# NODE_DW1000_B_V2.net
KiCad netlist of a schematic drawn in Altium Designer
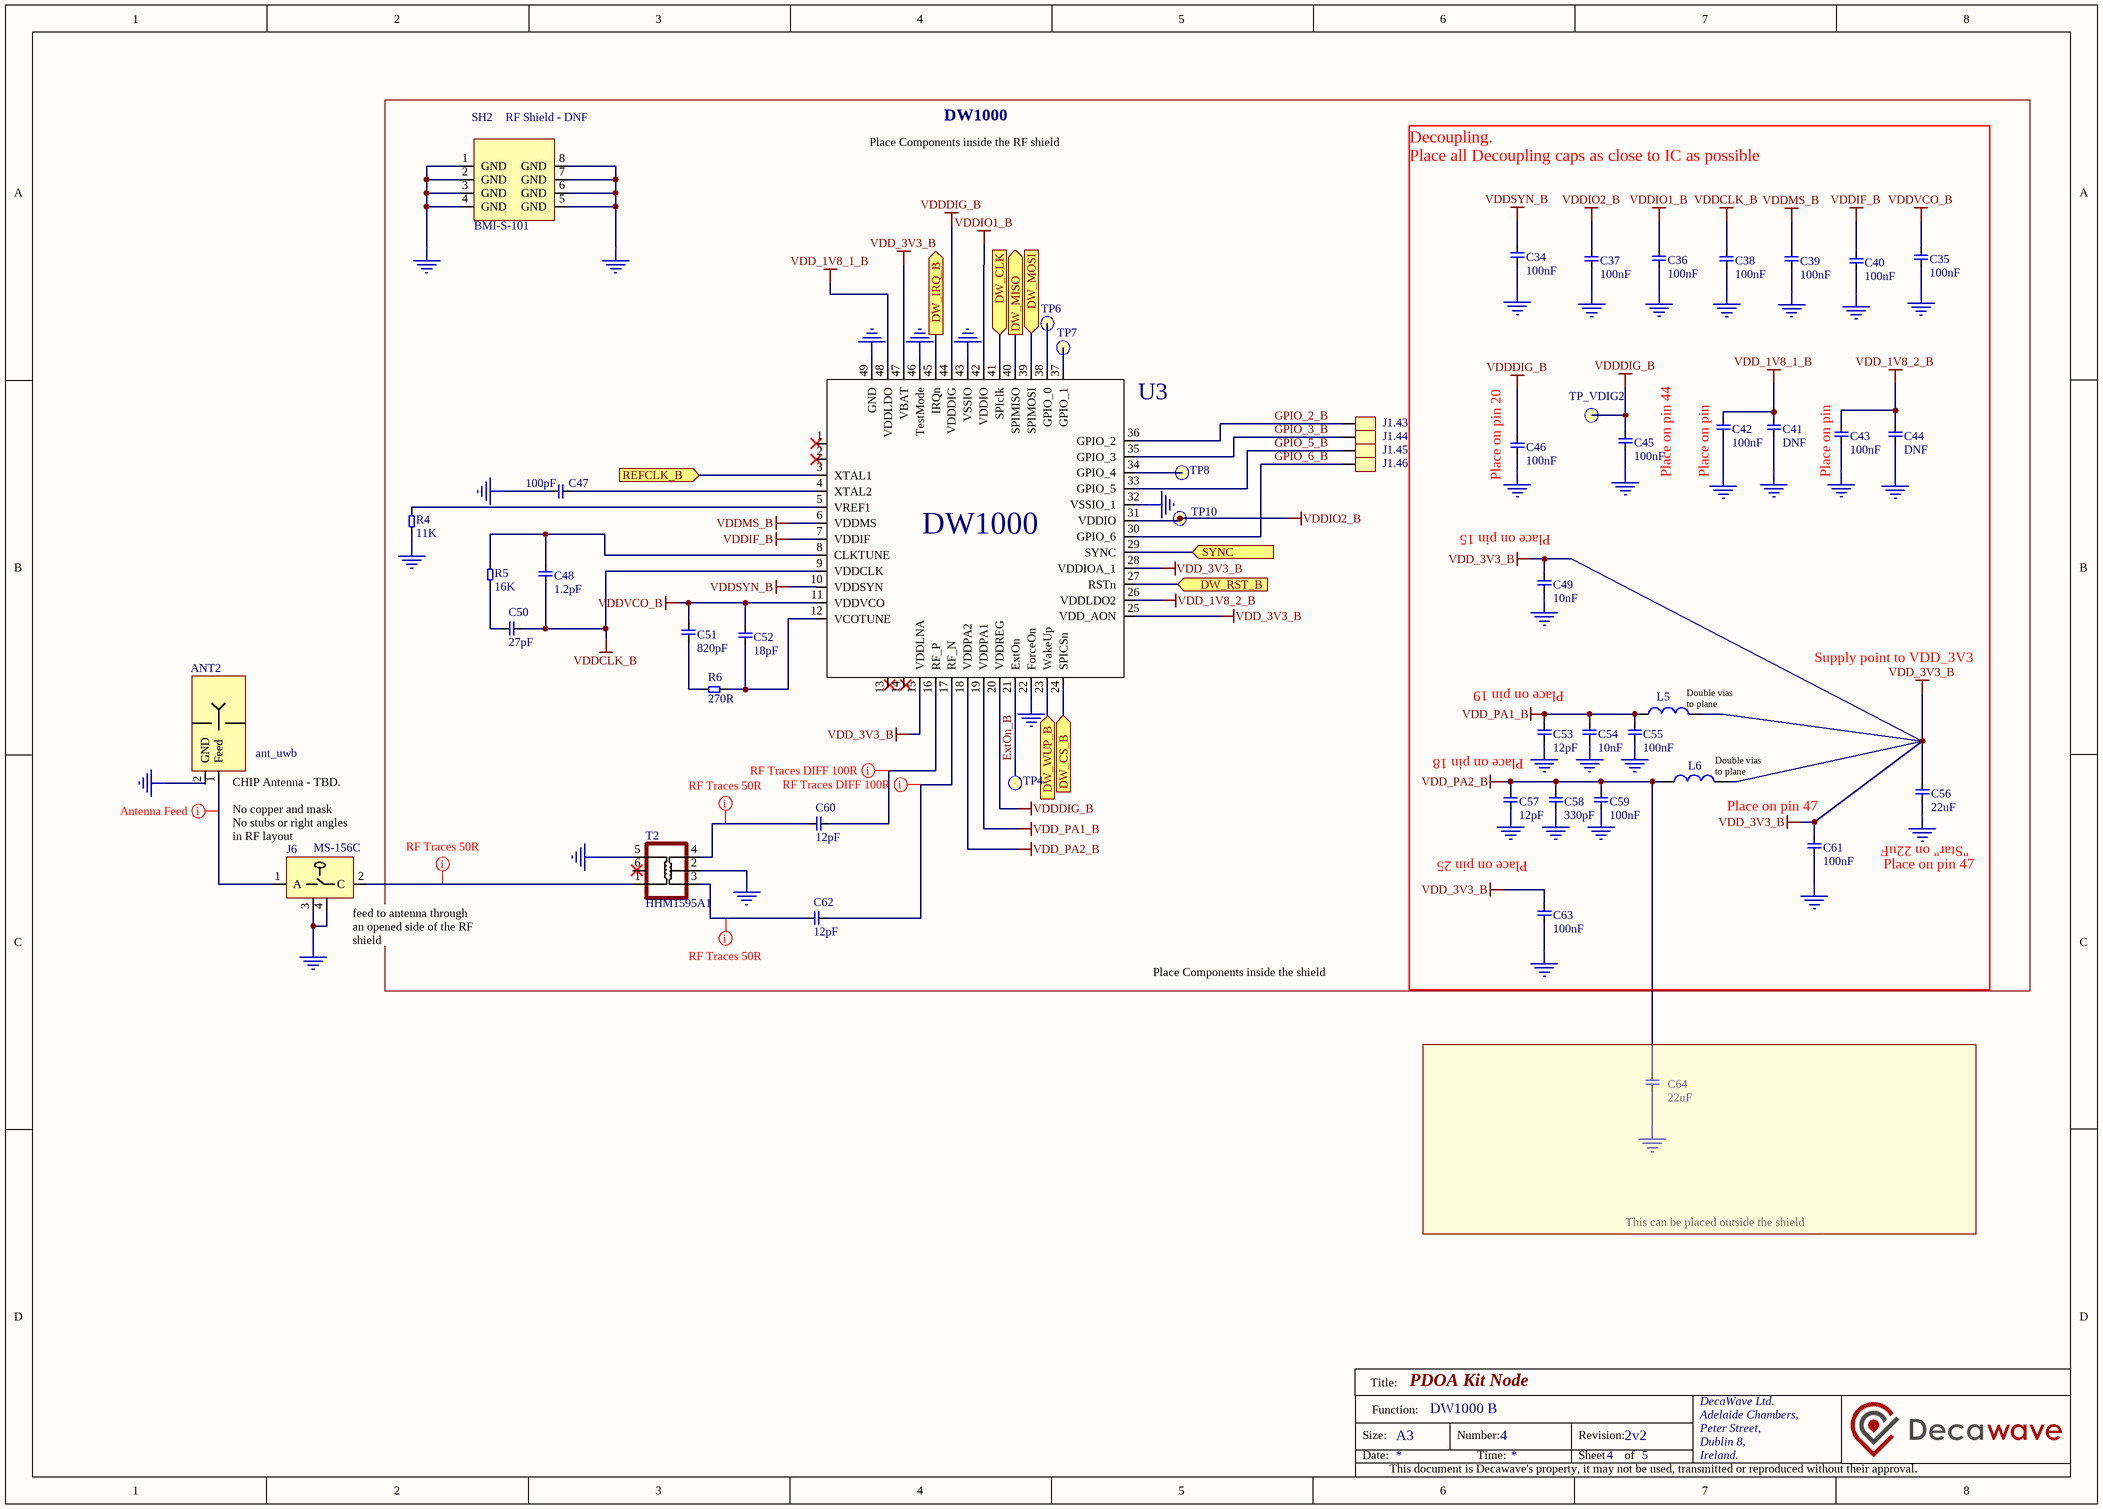
[diagram p0: NODE_DW1000_B_V2.SchDoc]

(export (version "E")
  (design (tool "Eeschema 10.0.6"))
  (components
    (comp (ref "ANT2")
      (value "ant_uwb")
      (footprint "ANT")
      (description "CHIP ANT")
      (libsource (lib "DecaWavedB") (part "ant_pcb"))
    )
    (comp (ref "C34")
      (value "100nF")
      (footprint "C0201-C")
      (description "100nF_0201_10%")
      (fields
        (field (name "MANUFACTURER") "Murata Electronics North America")
        (field (name "MANUFACTURER PART NUMBER") "GRM033C81E104KE14D")
      )
      (libsource (lib "DecaWavedB") (part "Capacitor - non polarized"))
    )
    (comp (ref "C35")
      (value "100nF")
      (footprint "C0201-C")
      (description "100nF_0201_10%")
      (fields
        (field (name "MANUFACTURER") "Murata Electronics North America")
        (field (name "MANUFACTURER PART NUMBER") "GRM033C81E104KE14D")
      )
      (libsource (lib "DecaWavedB") (part "Capacitor - non polarized"))
    )
    (comp (ref "C36")
      (value "100nF")
      (footprint "C0201-C")
      (description "100nF_0201_10%")
      (fields
        (field (name "MANUFACTURER") "Murata Electronics North America")
        (field (name "MANUFACTURER PART NUMBER") "GRM033C81E104KE14D")
      )
      (libsource (lib "DecaWavedB") (part "Capacitor - non polarized"))
    )
    (comp (ref "C37")
      (value "100nF")
      (footprint "C0201-C")
      (description "100nF_0201_10%")
      (fields
        (field (name "MANUFACTURER") "Murata Electronics North America")
        (field (name "MANUFACTURER PART NUMBER") "GRM033C81E104KE14D")
      )
      (libsource (lib "DecaWavedB") (part "Capacitor - non polarized"))
    )
    (comp (ref "C38")
      (value "100nF")
      (footprint "C0201-C")
      (description "100nF_0201_10%")
      (fields
        (field (name "MANUFACTURER") "Murata Electronics North America")
        (field (name "MANUFACTURER PART NUMBER") "GRM033C81E104KE14D")
      )
      (libsource (lib "DecaWavedB") (part "Capacitor - non polarized"))
    )
    (comp (ref "C39")
      (value "100nF")
      (footprint "C0201-C")
      (description "100nF_0201_10%")
      (fields
        (field (name "MANUFACTURER") "Murata Electronics North America")
        (field (name "MANUFACTURER PART NUMBER") "GRM033C81E104KE14D")
      )
      (libsource (lib "DecaWavedB") (part "Capacitor - non polarized"))
    )
    (comp (ref "C40")
      (value "100nF")
      (footprint "C0201-C")
      (description "100nF_0201_10%")
      (fields
        (field (name "MANUFACTURER") "Murata Electronics North America")
        (field (name "MANUFACTURER PART NUMBER") "GRM033C81E104KE14D")
      )
      (libsource (lib "DecaWavedB") (part "Capacitor - non polarized"))
    )
    (comp (ref "C41")
      (value "DNF")
      (footprint "C0402")
      (description "4.7uF_0402_10%")
      (fields
        (field (name "MANUFACTURER") "TDK")
        (field (name "MANUFACTURER PART NUMBER") "C1005X5R0J475K050BC")
      )
      (libsource (lib "DecaWavedB") (part "Capacitor - non polarized"))
    )
    (comp (ref "C42")
      (value "100nF")
      (footprint "C0201-C")
      (description "100nF_0201_10%")
      (fields
        (field (name "MANUFACTURER") "Murata Electronics North America")
        (field (name "MANUFACTURER PART NUMBER") "GRM033C81E104KE14D")
      )
      (libsource (lib "DecaWavedB") (part "Capacitor - non polarized"))
    )
    (comp (ref "C43")
      (value "100nF")
      (footprint "C0201-C")
      (description "100nF_0201_10%")
      (fields
        (field (name "MANUFACTURER") "Murata Electronics North America")
        (field (name "MANUFACTURER PART NUMBER") "GRM033C81E104KE14D")
      )
      (libsource (lib "DecaWavedB") (part "Capacitor - non polarized"))
    )
    (comp (ref "C44")
      (value "DNF")
      (footprint "C0402")
      (description "4.7uF_0402_10%")
      (fields
        (field (name "MANUFACTURER") "TDK")
        (field (name "MANUFACTURER PART NUMBER") "C1005X5R0J475K050BC")
      )
      (libsource (lib "DecaWavedB") (part "Capacitor - non polarized"))
    )
    (comp (ref "C45")
      (value "100nF")
      (footprint "C0201-C")
      (description "100nF_0201_10%")
      (fields
        (field (name "MANUFACTURER") "Murata Electronics North America")
        (field (name "MANUFACTURER PART NUMBER") "GRM033C81E104KE14D")
      )
      (libsource (lib "DecaWavedB") (part "Capacitor - non polarized"))
    )
    (comp (ref "C46")
      (value "100nF")
      (footprint "C0201-C")
      (description "100nF_0201_10%")
      (fields
        (field (name "MANUFACTURER") "Murata Electronics North America")
        (field (name "MANUFACTURER PART NUMBER") "GRM033C81E104KE14D")
      )
      (libsource (lib "DecaWavedB") (part "Capacitor - non polarized"))
    )
    (comp (ref "C47")
      (value "100pF")
      (footprint "C0402")
      (description "100pF_0402_10%")
      (fields
        (field (name "MANUFACTURER PART NUMBER") "GRM1555C1H101JA01D")
        (field (name "MANUFACTURER") "Murata Electronics North America")
      )
      (libsource (lib "DecaWavedB") (part "Capacitor - non polarized"))
    )
    (comp (ref "C48")
      (value "1.2pF")
      (footprint "C0201-C")
      (description "1.2pF_0201_10%")
      (fields
        (field (name "MANUFACTURER") "Murata Electronics North America")
        (field (name "MANUFACTURER PART NUMBER") "GRM0335C1E1R2CA01D")
      )
      (libsource (lib "DecaWavedB") (part "Capacitor - non polarized"))
    )
    (comp (ref "C49")
      (value "10nF")
      (footprint "C0201-C")
      (description "10nF_0201_10%")
      (fields
        (field (name "MANUFACTURER") "Murata Electronics North America")
        (field (name "MANUFACTURER PART NUMBER") "GRM033R61E103KA12D")
      )
      (libsource (lib "DecaWavedB") (part "Capacitor - non polarized"))
    )
    (comp (ref "C50")
      (value "27pF")
      (footprint "C0201-C")
      (description "27pF_0201_2%")
      (fields
        (field (name "MANUFACTURER") "Murata Electronics North America")
        (field (name "MANUFACTURER PART NUMBER") "GRM0335C1E270JA01D")
      )
      (libsource (lib "DecaWavedB") (part "Capacitor - non polarized"))
    )
    (comp (ref "C51")
      (value "820pF")
      (footprint "C0402")
      (description "820pF_0201_2%")
      (fields
        (field (name "MANUFACTURER") "Murata Electronics North America")
        (field (name "MANUFACTURER PART NUMBER") "GRM033R71E821KA01D")
      )
      (libsource (lib "DecaWavedB") (part "Capacitor - non polarized"))
    )
    (comp (ref "C52")
      (value "18pF")
      (footprint "C0201-C")
      (description "18pF_0201_1%")
      (fields
        (field (name "MANUFACTURER") "Murata Electronics North America")
        (field (name "MANUFACTURER PART NUMBER") "GRM0335C1H180JA01D")
      )
      (libsource (lib "DecaWavedB") (part "Capacitor - non polarized"))
    )
    (comp (ref "C53")
      (value "12pF")
      (footprint "C0201-C")
      (description "12pF_0201_1%")
      (fields
        (field (name "MANUFACTURER") "Murata Electronics North America")
        (field (name "MANUFACTURER PART NUMBER") "GRM0335C1E120JA01D")
      )
      (libsource (lib "DecaWavedB") (part "Capacitor - non polarized"))
    )
    (comp (ref "C54")
      (value "10nF")
      (footprint "C0201-C")
      (description "10nF_0201_10%")
      (fields
        (field (name "MANUFACTURER") "Murata Electronics North America")
        (field (name "MANUFACTURER PART NUMBER") "GRM033R61E103KA12D")
      )
      (libsource (lib "DecaWavedB") (part "Capacitor - non polarized"))
    )
    (comp (ref "C55")
      (value "100nF")
      (footprint "C0201-C")
      (description "100nF_0201_10%")
      (fields
        (field (name "MANUFACTURER") "Murata Electronics North America")
        (field (name "MANUFACTURER PART NUMBER") "GRM033C81E104KE14D")
      )
      (libsource (lib "DecaWavedB") (part "Capacitor - non polarized"))
    )
    (comp (ref "C56")
      (value "22uF")
      (footprint "C0603")
      (description "22uF_0603_10%")
      (fields
        (field (name "MANUFACTURER") "Murata Electronics North America")
        (field (name "MANUFACTURER PART NUMBER") "GRM188R60J226MEA0D")
      )
      (libsource (lib "DecaWavedB") (part "Capacitor - non polarized"))
    )
    (comp (ref "C57")
      (value "12pF")
      (footprint "C0201-C")
      (description "12pF_0201_1%")
      (fields
        (field (name "MANUFACTURER") "Murata Electronics North America")
        (field (name "MANUFACTURER PART NUMBER") "GRM0335C1E120JA01D")
      )
      (libsource (lib "DecaWavedB") (part "Capacitor - non polarized"))
    )
    (comp (ref "C58")
      (value "330pF")
      (footprint "C0201-C")
      (description "330pF_0201_10%")
      (fields
        (field (name "MANUFACTURER") "SamSung")
        (field (name "MANUFACTURER PART NUMBER") "CL03B331KA3NNNC")
      )
      (libsource (lib "DecaWavedB") (part "Capacitor - non polarized"))
    )
    (comp (ref "C59")
      (value "100nF")
      (footprint "C0201-C")
      (description "100nF_0201_10%")
      (fields
        (field (name "MANUFACTURER") "Murata Electronics North America")
        (field (name "MANUFACTURER PART NUMBER") "GRM033C81E104KE14D")
      )
      (libsource (lib "DecaWavedB") (part "Capacitor - non polarized"))
    )
    (comp (ref "C60")
      (value "12pF")
      (footprint "C0201-C")
      (description "12pF_0201_1%")
      (fields
        (field (name "MANUFACTURER") "Murata Electronics North America")
        (field (name "MANUFACTURER PART NUMBER") "GRM0335C1E120JA01D")
      )
      (libsource (lib "DecaWavedB") (part "Capacitor - non polarized"))
    )
    (comp (ref "C61")
      (value "100nF")
      (footprint "C0201-C")
      (description "100nF_0201_10%")
      (fields
        (field (name "MANUFACTURER") "Murata Electronics North America")
        (field (name "MANUFACTURER PART NUMBER") "GRM033C81E104KE14D")
      )
      (libsource (lib "DecaWavedB") (part "Capacitor - non polarized"))
    )
    (comp (ref "C62")
      (value "12pF")
      (footprint "C0201-C")
      (description "12pF_0201_1%")
      (fields
        (field (name "MANUFACTURER") "Murata Electronics North America")
        (field (name "MANUFACTURER PART NUMBER") "GRM0335C1E120JA01D")
      )
      (libsource (lib "DecaWavedB") (part "Capacitor - non polarized"))
    )
    (comp (ref "C63")
      (value "100nF")
      (footprint "C0201-C")
      (description "100nF_0201_10%")
      (fields
        (field (name "MANUFACTURER") "Murata Electronics North America")
        (field (name "MANUFACTURER PART NUMBER") "GRM033C81E104KE14D")
      )
      (libsource (lib "DecaWavedB") (part "Capacitor - non polarized"))
    )
    (comp (ref "C64")
      (value "22uF")
      (footprint "C0603")
      (description "22uF_0603_10%")
      (fields
        (field (name "MANUFACTURER") "Murata Electronics North America")
        (field (name "MANUFACTURER PART NUMBER") "GRM188R60J226MEA0D")
      )
      (libsource (lib "DecaWavedB") (part "Capacitor - non polarized"))
    )
    (comp (ref "J1.43")
      (value "EDGE_PIN")
      (footprint "PCB_EDGE_1MM")
      (description "PCB Edge pin")
      (libsource (lib "drak_Library") (part "PCB_EDGE_1MM"))
    )
    (comp (ref "J1.44")
      (value "EDGE_PIN")
      (footprint "PCB_EDGE_1MM")
      (description "PCB Edge pin")
      (libsource (lib "drak_Library") (part "PCB_EDGE_1MM"))
    )
    (comp (ref "J1.45")
      (value "EDGE_PIN")
      (footprint "PCB_EDGE_1MM")
      (description "PCB Edge pin")
      (libsource (lib "drak_Library") (part "PCB_EDGE_1MM"))
    )
    (comp (ref "J1.46")
      (value "EDGE_PIN")
      (footprint "PCB_EDGE_1MM")
      (description "PCB Edge pin")
      (libsource (lib "drak_Library") (part "PCB_EDGE_1MM"))
    )
    (comp (ref "J6")
      (value "coswitch")
      (footprint "RF_SWITCH_2P3X2P3")
      (description "COAX JACK STR 50 OHM SMD")
      (fields (field (name "MANUFACTURER PART NUMBER") "MS-156C") (field (name "MANUFACTURER") "Hirose"))
      (libsource (lib "DecaWavedB") (part "coswitch"))
    )
    (comp (ref "L5")
      (value "BLM15HG601SN1D")
      (footprint "L0402")
      (description "FERRITE BEAD, 0.7OHM, 300MA, 0402")
      (fields (field (name "MANUFACTURER") "Murata Electronics North America"))
      (libsource (lib "DecaWavedB") (part "inductor"))
    )
    (comp (ref "L6")
      (value "BLM15HG601SN1D")
      (footprint "L0402")
      (description "FERRITE BEAD, 0.7OHM, 300MA, 0402")
      (fields (field (name "MANUFACTURER") "Murata Electronics North America"))
      (libsource (lib "DecaWavedB") (part "inductor"))
    )
    (comp (ref "R4")
      (value "11K")
      (footprint "R0201-C")
      (description "11K_0201_1%")
      (fields
        (field (name "MANUFACTURER") "Yageo")
        (field (name "MANUFACTURER PART NUMBER") "RC0201FR-0711KL")
      )
      (libsource (lib "DecaWavedB") (part "Resistor"))
    )
    (comp (ref "R5")
      (value "16K")
      (footprint "R0201-C")
      (description "16K_0201_1%")
      (fields
        (field (name "MANUFACTURER") "Yageo")
        (field (name "MANUFACTURER PART NUMBER") "RC0201FR-0716KL")
      )
      (libsource (lib "DecaWavedB") (part "Resistor"))
    )
    (comp (ref "R6")
      (value "270R")
      (footprint "R0201-C")
      (description "270R_0201_1%")
      (fields
        (field (name "MANUFACTURER") "Yageo")
        (field (name "MANUFACTURER PART NUMBER") "RC0201FR-07270RL")
      )
      (libsource (lib "DecaWavedB") (part "Resistor"))
    )
    (comp (ref "SH2")
      (value "BMI-S-101")
      (footprint "RF_SH_12P7X13P66")
      (description "RF Shield 13.66x12.1mm")
      (fields (field (name "MANUFACTURER") "Laird"))
      (libsource (lib "DecaWavedB") (part "bmi_s_202_f"))
    )
    (comp (ref "T2")
      (value "HHM1595A1")
      (footprint "TRANS4_0P65_2P15X1P4")
      (description "SMT UWB Balun 3-8Ghz")
      (fields (field (name "MANUFACTURER") "TDK"))
      (libsource (lib "DecaWavedB") (part "HHM1595A1"))
    )
    (comp (ref "TP4")
      (value "TP")
      (footprint "TP_40S")
      (description "test point")
      (libsource (lib "AoAB") (part "TP"))
    )
    (comp (ref "TP6")
      (value "TP")
      (footprint "TP_40S")
      (description "test point")
      (libsource (lib "AoAB") (part "TP"))
    )
    (comp (ref "TP7")
      (value "TP")
      (footprint "TP_40S")
      (description "test point")
      (libsource (lib "AoAB") (part "TP"))
    )
    (comp (ref "TP8")
      (value "TP")
      (footprint "TP_40S")
      (description "test point")
      (libsource (lib "AoAB") (part "TP"))
    )
    (comp (ref "TP10")
      (value "TP")
      (footprint "TP_40S")
      (description "test point")
      (libsource (lib "AoAB") (part "TP"))
    )
    (comp (ref "TP_VDIG2")
      (value "TP")
      (footprint "TP_40S")
      (description "test point")
      (libsource (lib "AoAB") (part "TP"))
    )
    (comp (ref "U3")
      (value "DW1000 IC")
      (footprint "QFN48_0P4_6P0X6P0_T")
      (description "UMB Transceiver")
      (fields (field (name "MANUFACTURER PART NUMBER") "DW1000") (field (name "MANUFACTURER") "Decawave"))
      (libsource (lib "DecaWavedB") (part "DW1000_QFN_48"))
    )
  )
  (nets
    (net (code "1") (name "/DW_CLK") (class "Default")
      (node (ref "U3") (pin "41") (pinfunction "SPIclk_41") (pintype "passive"))
    )
    (net (code "2") (name "/DW_CS_B") (class "Default")
      (node (ref "U3") (pin "24") (pinfunction "SPICSn_24") (pintype "passive"))
    )
    (net (code "3") (name "/DW_IRQ_B") (class "Default")
      (node (ref "U3") (pin "45") (pinfunction "IRQn_45") (pintype "passive"))
    )
    (net (code "4") (name "/DW_MISO") (class "Default")
      (node (ref "U3") (pin "40") (pinfunction "SPIMISO_40") (pintype "passive"))
    )
    (net (code "5") (name "/DW_MOSI") (class "Default")
      (node (ref "U3") (pin "39") (pinfunction "SPIMOSI_39") (pintype "passive"))
    )
    (net (code "6") (name "/DW_RST_B") (class "Default")
      (node (ref "U3") (pin "27") (pinfunction "RSTn_27") (pintype "passive"))
    )
    (net (code "7") (name "/DW_WUP_B") (class "Default")
      (node (ref "U3") (pin "23") (pinfunction "WakeUp_23") (pintype "passive"))
    )
    (net (code "8") (name "/ExtOn_B") (class "Default")
      (node (ref "TP4") (pin "1") (pinfunction "1_1") (pintype "passive"))
      (node (ref "U3") (pin "21") (pinfunction "ExtOn_21") (pintype "passive"))
    )
    (net (code "9") (name "/GPIO_2_B") (class "Default")
      (node (ref "J1.43") (pin "0") (pinfunction "0_0") (pintype "passive"))
      (node (ref "U3") (pin "36") (pinfunction "GPIO_2_36") (pintype "passive"))
    )
    (net (code "10") (name "/GPIO_3_B") (class "Default")
      (node (ref "J1.44") (pin "0") (pinfunction "0_0") (pintype "passive"))
      (node (ref "U3") (pin "35") (pinfunction "GPIO_3_35") (pintype "passive"))
    )
    (net (code "11") (name "/GPIO_5_B") (class "Default")
      (node (ref "J1.45") (pin "0") (pinfunction "0_0") (pintype "passive"))
      (node (ref "U3") (pin "33") (pinfunction "GPIO_5_33") (pintype "passive"))
    )
    (net (code "12") (name "/GPIO_6_B") (class "Default")
      (node (ref "J1.46") (pin "0") (pinfunction "0_0") (pintype "passive"))
      (node (ref "U3") (pin "30") (pinfunction "GPIO_6_30") (pintype "passive"))
    )
    (net (code "13") (name "/REFCLK_B") (class "Default")
      (node (ref "U3") (pin "3") (pinfunction "XTAL1_3") (pintype "passive"))
    )
    (net (code "14") (name "/SYNC") (class "Default")
      (node (ref "U3") (pin "29") (pinfunction "SYNC_29") (pintype "passive"))
    )
    (net (code "15") (name "GND") (class "Default")
      (node (ref "ANT2") (pin "2") (pinfunction "GND_2") (pintype "passive"))
      (node (ref "C34") (pin "1") (pinfunction "1_1") (pintype "passive"))
      (node (ref "C35") (pin "1") (pinfunction "1_1") (pintype "passive"))
      (node (ref "C36") (pin "1") (pinfunction "1_1") (pintype "passive"))
      (node (ref "C37") (pin "1") (pinfunction "1_1") (pintype "passive"))
      (node (ref "C38") (pin "1") (pinfunction "1_1") (pintype "passive"))
      (node (ref "C39") (pin "1") (pinfunction "1_1") (pintype "passive"))
      (node (ref "C40") (pin "1") (pinfunction "1_1") (pintype "passive"))
      (node (ref "C41") (pin "1") (pinfunction "1_1") (pintype "passive"))
      (node (ref "C42") (pin "1") (pinfunction "1_1") (pintype "passive"))
      (node (ref "C43") (pin "1") (pinfunction "1_1") (pintype "passive"))
      (node (ref "C44") (pin "1") (pinfunction "1_1") (pintype "passive"))
      (node (ref "C45") (pin "1") (pinfunction "1_1") (pintype "passive"))
      (node (ref "C46") (pin "1") (pinfunction "1_1") (pintype "passive"))
      (node (ref "C47") (pin "2") (pinfunction "2_2") (pintype "passive"))
      (node (ref "C49") (pin "1") (pinfunction "1_1") (pintype "passive"))
      (node (ref "C53") (pin "1") (pinfunction "1_1") (pintype "passive"))
      (node (ref "C54") (pin "1") (pinfunction "1_1") (pintype "passive"))
      (node (ref "C55") (pin "1") (pinfunction "1_1") (pintype "passive"))
      (node (ref "C56") (pin "1") (pinfunction "1_1") (pintype "passive"))
      (node (ref "C57") (pin "1") (pinfunction "1_1") (pintype "passive"))
      (node (ref "C58") (pin "1") (pinfunction "1_1") (pintype "passive"))
      (node (ref "C59") (pin "1") (pinfunction "1_1") (pintype "passive"))
      (node (ref "C61") (pin "1") (pinfunction "1_1") (pintype "passive"))
      (node (ref "C63") (pin "1") (pinfunction "1_1") (pintype "passive"))
      (node (ref "C64") (pin "1") (pinfunction "1_1") (pintype "passive"))
      (node (ref "J6") (pin "3") (pinfunction "GND_3") (pintype "passive"))
      (node (ref "J6") (pin "4") (pinfunction "GND_4") (pintype "passive"))
      (node (ref "R4") (pin "1") (pinfunction "1_1") (pintype "passive"))
      (node (ref "SH2") (pin "1") (pinfunction "GND_1") (pintype "passive"))
      (node (ref "SH2") (pin "2") (pinfunction "GND_2") (pintype "passive"))
      (node (ref "SH2") (pin "3") (pinfunction "GND_3") (pintype "passive"))
      (node (ref "SH2") (pin "4") (pinfunction "GND_4") (pintype "passive"))
      (node (ref "SH2") (pin "5") (pinfunction "GND_5") (pintype "passive"))
      (node (ref "SH2") (pin "6") (pinfunction "GND_6") (pintype "passive"))
      (node (ref "SH2") (pin "7") (pinfunction "GND_7") (pintype "passive"))
      (node (ref "SH2") (pin "8") (pinfunction "GND_8") (pintype "passive"))
      (node (ref "T2") (pin "2") (pinfunction "2_2") (pintype "passive"))
      (node (ref "T2") (pin "5") (pinfunction "5_5") (pintype "passive"))
      (node (ref "U3") (pin "22") (pinfunction "ForceOn_22") (pintype "passive"))
      (node (ref "U3") (pin "32") (pinfunction "VSSIO_1_32") (pintype "passive"))
      (node (ref "U3") (pin "43") (pinfunction "VSSIO_43") (pintype "passive"))
      (node (ref "U3") (pin "46") (pinfunction "TestMode_46") (pintype "passive"))
      (node (ref "U3") (pin "49") (pinfunction "GND_49") (pintype "passive"))
    )
    (net (code "16") (name "Net-(ANT2-Feed)") (class "Default")
      (node (ref "ANT2") (pin "1") (pinfunction "Feed_1") (pintype "passive"))
      (node (ref "J6") (pin "1") (pinfunction "A_1") (pintype "passive"))
    )
    (net (code "17") (name "Net-(C50-Pad2)") (class "Default")
      (node (ref "C50") (pin "2") (pinfunction "2_2") (pintype "passive"))
      (node (ref "R5") (pin "1") (pinfunction "1_1") (pintype "passive"))
    )
    (net (code "18") (name "Net-(C51-Pad1)") (class "Default")
      (node (ref "C51") (pin "1") (pinfunction "1_1") (pintype "passive"))
      (node (ref "R6") (pin "2") (pinfunction "2_2") (pintype "passive"))
    )
    (net (code "19") (name "Net-(C60-Pad1)") (class "Default")
      (node (ref "C60") (pin "1") (pinfunction "1_1") (pintype "passive"))
      (node (ref "T2") (pin "4") (pinfunction "4_4") (pintype "passive"))
    )
    (net (code "20") (name "Net-(C62-Pad1)") (class "Default")
      (node (ref "C62") (pin "1") (pinfunction "1_1") (pintype "passive"))
      (node (ref "T2") (pin "3") (pinfunction "3_3") (pintype "passive"))
    )
    (net (code "21") (name "Net-(J6-C)") (class "Default")
      (node (ref "J6") (pin "2") (pinfunction "C_2") (pintype "passive"))
      (node (ref "T2") (pin "1") (pinfunction "1_1") (pintype "passive"))
    )
    (net (code "22") (name "Net-(U3-CLKTUNE)") (class "Default")
      (node (ref "C48") (pin "2") (pinfunction "2_2") (pintype "passive"))
      (node (ref "R5") (pin "2") (pinfunction "2_2") (pintype "passive"))
      (node (ref "U3") (pin "8") (pinfunction "CLKTUNE_8") (pintype "passive"))
    )
    (net (code "23") (name "Net-(U3-GPIO_0)") (class "Default")
      (node (ref "TP6") (pin "1") (pinfunction "1_1") (pintype "passive"))
      (node (ref "U3") (pin "38") (pinfunction "GPIO_0_38") (pintype "passive"))
    )
    (net (code "24") (name "Net-(U3-GPIO_1)") (class "Default")
      (node (ref "TP7") (pin "1") (pinfunction "1_1") (pintype "passive"))
      (node (ref "U3") (pin "37") (pinfunction "GPIO_1_37") (pintype "passive"))
    )
    (net (code "25") (name "Net-(U3-GPIO_4)") (class "Default")
      (node (ref "TP8") (pin "1") (pinfunction "1_1") (pintype "passive"))
      (node (ref "U3") (pin "34") (pinfunction "GPIO_4_34") (pintype "passive"))
    )
    (net (code "26") (name "Net-(U3-RF_N)") (class "Default")
      (node (ref "C62") (pin "2") (pinfunction "2_2") (pintype "passive"))
      (node (ref "U3") (pin "17") (pinfunction "RF_N_17") (pintype "passive"))
    )
    (net (code "27") (name "Net-(U3-RF_P)") (class "Default")
      (node (ref "C60") (pin "2") (pinfunction "2_2") (pintype "passive"))
      (node (ref "U3") (pin "16") (pinfunction "RF_P_16") (pintype "passive"))
    )
    (net (code "28") (name "Net-(U3-VCOTUNE)") (class "Default")
      (node (ref "C52") (pin "2") (pinfunction "2_2") (pintype "passive"))
      (node (ref "R6") (pin "1") (pinfunction "1_1") (pintype "passive"))
      (node (ref "U3") (pin "12") (pinfunction "VCOTUNE_12") (pintype "passive"))
    )
    (net (code "29") (name "Net-(U3-VREF1)") (class "Default")
      (node (ref "R4") (pin "2") (pinfunction "2_2") (pintype "passive"))
      (node (ref "U3") (pin "5") (pinfunction "VREF1_5") (pintype "passive"))
    )
    (net (code "30") (name "Net-(U3-XTAL2)") (class "Default")
      (node (ref "C47") (pin "1") (pinfunction "1_1") (pintype "passive"))
      (node (ref "U3") (pin "4") (pinfunction "XTAL2_4") (pintype "passive"))
    )
    (net (code "31") (name "VDDCLK_B") (class "Default")
      (node (ref "C38") (pin "2") (pinfunction "2_2") (pintype "passive"))
      (node (ref "C48") (pin "1") (pinfunction "1_1") (pintype "passive"))
      (node (ref "C50") (pin "1") (pinfunction "1_1") (pintype "passive"))
      (node (ref "U3") (pin "9") (pinfunction "VDDCLK_9") (pintype "passive"))
    )
    (net (code "32") (name "VDDDIG_B") (class "Default")
      (node (ref "C45") (pin "2") (pinfunction "2_2") (pintype "passive"))
      (node (ref "C46") (pin "2") (pinfunction "2_2") (pintype "passive"))
      (node (ref "TP_VDIG2") (pin "1") (pinfunction "1_1") (pintype "passive"))
      (node (ref "U3") (pin "20") (pinfunction "VDDREG_20") (pintype "passive"))
      (node (ref "U3") (pin "44") (pinfunction "VDDDIG_44") (pintype "passive"))
    )
    (net (code "33") (name "VDDIF_B") (class "Default")
      (node (ref "C40") (pin "2") (pinfunction "2_2") (pintype "passive"))
      (node (ref "U3") (pin "7") (pinfunction "VDDIF_7") (pintype "passive"))
    )
    (net (code "34") (name "VDDIO1_B") (class "Default")
      (node (ref "C36") (pin "2") (pinfunction "2_2") (pintype "passive"))
      (node (ref "U3") (pin "42") (pinfunction "VDDIO_42") (pintype "passive"))
    )
    (net (code "35") (name "VDDIO2_B") (class "Default")
      (node (ref "C37") (pin "2") (pinfunction "2_2") (pintype "passive"))
      (node (ref "TP10") (pin "1") (pinfunction "1_1") (pintype "passive"))
      (node (ref "U3") (pin "31") (pinfunction "VDDIO_31") (pintype "passive"))
    )
    (net (code "36") (name "VDDMS_B") (class "Default")
      (node (ref "C39") (pin "2") (pinfunction "2_2") (pintype "passive"))
      (node (ref "U3") (pin "6") (pinfunction "VDDMS_6") (pintype "passive"))
    )
    (net (code "37") (name "VDDSYN_B") (class "Default")
      (node (ref "C34") (pin "2") (pinfunction "2_2") (pintype "passive"))
      (node (ref "U3") (pin "10") (pinfunction "VDDSYN_10") (pintype "passive"))
    )
    (net (code "38") (name "VDDVCO_B") (class "Default")
      (node (ref "C35") (pin "2") (pinfunction "2_2") (pintype "passive"))
      (node (ref "C51") (pin "2") (pinfunction "2_2") (pintype "passive"))
      (node (ref "C52") (pin "1") (pinfunction "1_1") (pintype "passive"))
      (node (ref "U3") (pin "11") (pinfunction "VDDVCO_11") (pintype "passive"))
    )
    (net (code "39") (name "VDD_1V8_1_B") (class "Default")
      (node (ref "C41") (pin "2") (pinfunction "2_2") (pintype "passive"))
      (node (ref "C42") (pin "2") (pinfunction "2_2") (pintype "passive"))
      (node (ref "U3") (pin "48") (pinfunction "VDDLDO_48") (pintype "passive"))
    )
    (net (code "40") (name "VDD_1V8_2_B") (class "Default")
      (node (ref "C43") (pin "2") (pinfunction "2_2") (pintype "passive"))
      (node (ref "C44") (pin "2") (pinfunction "2_2") (pintype "passive"))
      (node (ref "U3") (pin "26") (pinfunction "VDDLDO2_26") (pintype "passive"))
    )
    (net (code "41") (name "VDD_3V3_B") (class "Default")
      (node (ref "C49") (pin "2") (pinfunction "2_2") (pintype "passive"))
      (node (ref "C56") (pin "2") (pinfunction "2_2") (pintype "passive"))
      (node (ref "C61") (pin "2") (pinfunction "2_2") (pintype "passive"))
      (node (ref "C63") (pin "2") (pinfunction "2_2") (pintype "passive"))
      (node (ref "L5") (pin "2") (pinfunction "2_2") (pintype "passive"))
      (node (ref "L6") (pin "2") (pinfunction "2_2") (pintype "passive"))
      (node (ref "U3") (pin "15") (pinfunction "VDDLNA_15") (pintype "passive"))
      (node (ref "U3") (pin "25") (pinfunction "VDD_AON_25") (pintype "passive"))
      (node (ref "U3") (pin "28") (pinfunction "VDDIOA_1_28") (pintype "passive"))
      (node (ref "U3") (pin "47") (pinfunction "VBAT_47") (pintype "passive"))
    )
    (net (code "42") (name "VDD_PA1_B") (class "Default")
      (node (ref "C53") (pin "2") (pinfunction "2_2") (pintype "passive"))
      (node (ref "C54") (pin "2") (pinfunction "2_2") (pintype "passive"))
      (node (ref "C55") (pin "2") (pinfunction "2_2") (pintype "passive"))
      (node (ref "L5") (pin "1") (pinfunction "1_1") (pintype "passive"))
      (node (ref "U3") (pin "19") (pinfunction "VDDPA1_19") (pintype "passive"))
    )
    (net (code "43") (name "VDD_PA2_B") (class "Default")
      (node (ref "C57") (pin "2") (pinfunction "2_2") (pintype "passive"))
      (node (ref "C58") (pin "2") (pinfunction "2_2") (pintype "passive"))
      (node (ref "C59") (pin "2") (pinfunction "2_2") (pintype "passive"))
      (node (ref "C64") (pin "2") (pinfunction "2_2") (pintype "passive"))
      (node (ref "L6") (pin "1") (pinfunction "1_1") (pintype "passive"))
      (node (ref "U3") (pin "18") (pinfunction "VDDPA2_18") (pintype "passive"))
    )
    (net (code "44") (name "unconnected-(T2-Pad6)") (class "Default")
      (node (ref "T2") (pin "6") (pinfunction "6_6") (pintype "passive"))
    )
    (net (code "45") (name "unconnected-(U3-Pad1)") (class "Default")
      (node (ref "U3") (pin "1") (pintype "passive"))
    )
    (net (code "46") (name "unconnected-(U3-Pad2)") (class "Default")
      (node (ref "U3") (pin "2") (pintype "passive"))
    )
    (net (code "47") (name "unconnected-(U3-Pad13)") (class "Default")
      (node (ref "U3") (pin "13") (pintype "passive"))
    )
    (net (code "48") (name "unconnected-(U3-Pad14)") (class "Default")
      (node (ref "U3") (pin "14") (pintype "passive"))
    )
  )
)
